# BMS_Rev3_SSR.net
KiCad netlist of a schematic drawn in EAGLE
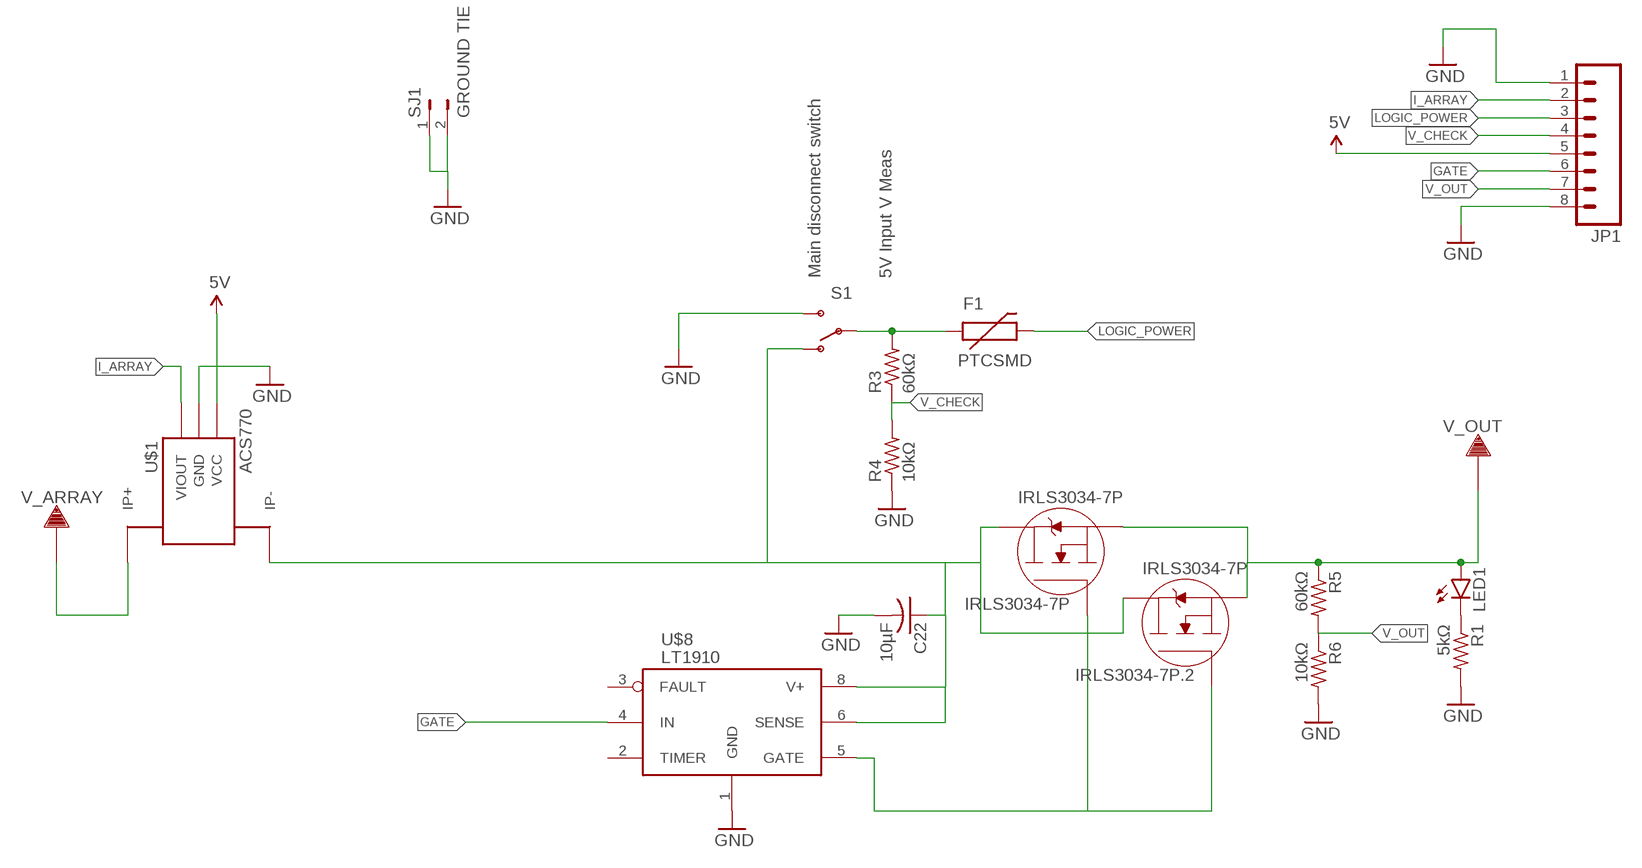
[diagram p0: schematic, sheet 1]

(export (version "E")
  (design (tool "Eeschema 10.0.6"))
  (components
    (comp (ref "C22")
      (value "10µF")
      (footprint "eagle-import:C1206")
      (libsource (lib "eagle-import") (part "C-USC1206"))
    )
    (comp (ref "F1")
      (value "PTCSMD")
      (footprint "eagle-import:PTC-1206")
      (libsource (lib "eagle-import") (part "PTCSMD"))
    )
    (comp (ref "IRLS3034-7P")
      (value "IRLS3034-7P")
      (footprint "eagle-import:D2PAK-7")
      (libsource (lib "eagle-import") (part "IRLS3034-7P"))
    )
    (comp (ref "IRLS3034-7P.2")
      (value "IRLS3034-7P")
      (footprint "eagle-import:D2PAK-7")
      (libsource (lib "eagle-import") (part "IRLS3034-7P"))
    )
    (comp (ref "JP1")
      (value "M08BM08B-SRSS-TB")
      (footprint "eagle-import:BM08B-SRSS-TB")
      (libsource (lib "eagle-import") (part "M08BM08B-SRSS-TB"))
    )
    (comp (ref "LED1")
      (value "LED1206")
      (footprint "eagle-import:LED-1206")
      (libsource (lib "eagle-import") (part "LED1206"))
    )
    (comp (ref "R1")
      (value "5kΩ")
      (footprint "eagle-import:R1206")
      (libsource (lib "eagle-import") (part "R-US_R1206"))
    )
    (comp (ref "R3")
      (value "60kΩ")
      (footprint "eagle-import:R1206")
      (libsource (lib "eagle-import") (part "R-US_R1206"))
    )
    (comp (ref "R4")
      (value "10kΩ")
      (footprint "eagle-import:R1206")
      (libsource (lib "eagle-import") (part "R-US_R1206"))
    )
    (comp (ref "R5")
      (value "60kΩ")
      (footprint "eagle-import:R1206")
      (libsource (lib "eagle-import") (part "R-US_R1206"))
    )
    (comp (ref "R6")
      (value "10kΩ")
      (footprint "eagle-import:R1206")
      (libsource (lib "eagle-import") (part "R-US_R1206"))
    )
    (comp (ref "S1")
      (value "SWITCH-SPDTPTH")
      (footprint "eagle-import:SWITCH-SPDT")
      (libsource (lib "eagle-import") (part "SWITCH-SPDTPTH"))
    )
    (comp (ref "SJ1")
      (value "GROUND TIE")
      (footprint "eagle-import:PTH-JUMPER-2-NO_NO_SILK")
      (libsource (lib "eagle-import") (part "JUMPER-PTH-2-NO"))
    )
    (comp (ref "U$1")
      (value "ACS770")
      (footprint "eagle-import:PFF_LEADFORM")
      (libsource (lib "eagle-import") (part "ACS770"))
    )
    (comp (ref "U$8")
      (value "LT1910")
      (footprint "eagle-import:SO8")
      (libsource (lib "eagle-import") (part "LT1910"))
    )
    (comp (ref "V_ARRAY")
      (value "TERMINAL_HOLE")
      (footprint "eagle-import:LARGE_TERMINAL_HOLE")
      (libsource (lib "eagle-import") (part "TERMINAL_HOLE"))
    )
    (comp (ref "V_OUT")
      (value "TERMINAL_HOLE")
      (footprint "eagle-import:LARGE_TERMINAL_HOLE")
      (libsource (lib "eagle-import") (part "TERMINAL_HOLE"))
    )
  )
  (nets
    (net (code "1") (name "5V") (class "Default")
      (node (ref "JP1") (pin "5") (pinfunction "5_5") (pintype "passive"))
      (node (ref "U$1") (pin "1") (pinfunction "VCC_1") (pintype "bidirectional"))
    )
    (net (code "2") (name "GATE") (class "Default")
      (node (ref "JP1") (pin "6") (pinfunction "6_6") (pintype "passive"))
      (node (ref "U$8") (pin "4") (pinfunction "IN_4") (pintype "bidirectional"))
    )
    (net (code "3") (name "GND") (class "Default")
      (node (ref "C22") (pin "2") (pinfunction "2_2") (pintype "passive"))
      (node (ref "JP1") (pin "1") (pinfunction "1_1") (pintype "passive"))
      (node (ref "JP1") (pin "8") (pinfunction "8_8") (pintype "passive"))
      (node (ref "R1") (pin "2") (pinfunction "2_2") (pintype "passive"))
      (node (ref "R4") (pin "1") (pinfunction "1_1") (pintype "passive"))
      (node (ref "R6") (pin "2") (pinfunction "2_2") (pintype "passive"))
      (node (ref "S1") (pin "3") (pinfunction "S_3") (pintype "passive"))
      (node (ref "SJ1") (pin "1") (pinfunction "1_1") (pintype "passive"))
      (node (ref "SJ1") (pin "2") (pinfunction "2_2") (pintype "passive"))
      (node (ref "U$1") (pin "2") (pinfunction "GND_2") (pintype "bidirectional"))
      (node (ref "U$8") (pin "1") (pinfunction "GND_1") (pintype "bidirectional"))
    )
    (net (code "4") (name "I_ARRAY") (class "Default")
      (node (ref "JP1") (pin "2") (pinfunction "2_2") (pintype "passive"))
      (node (ref "U$1") (pin "3") (pinfunction "VIOUT_3") (pintype "bidirectional"))
    )
    (net (code "5") (name "LOGIC_POWER") (class "Default")
      (node (ref "F1") (pin "2") (pinfunction "2_2") (pintype "bidirectional"))
      (node (ref "JP1") (pin "3") (pinfunction "3_3") (pintype "passive"))
    )
    (net (code "6") (name "Net-(IRLS3034-7P-DRAIN)") (class "Default")
      (node (ref "C22") (pin "1") (pinfunction "1_1") (pintype "passive"))
      (node (ref "IRLS3034-7P") (pin "PAD") (pinfunction "DRAIN_PAD") (pintype "bidirectional"))
      (node (ref "IRLS3034-7P.2") (pin "PAD") (pinfunction "DRAIN_PAD") (pintype "bidirectional"))
      (node (ref "S1") (pin "1") (pinfunction "O_1") (pintype "passive"))
      (node (ref "U$1") (pin "5_1") (pinfunction "IP-_5_1") (pintype "bidirectional"))
      (node (ref "U$1") (pin "5_10") (pinfunction "IP-_5_10") (pintype "bidirectional"))
      (node (ref "U$1") (pin "5_11") (pinfunction "IP-_5_11") (pintype "bidirectional"))
      (node (ref "U$1") (pin "5_12") (pinfunction "IP-_5_12") (pintype "bidirectional"))
      (node (ref "U$1") (pin "5_13") (pinfunction "IP-_5_13") (pintype "bidirectional"))
      (node (ref "U$1") (pin "5_14") (pinfunction "IP-_5_14") (pintype "bidirectional"))
      (node (ref "U$1") (pin "5_15") (pinfunction "IP-_5_15") (pintype "bidirectional"))
      (node (ref "U$1") (pin "5_16") (pinfunction "IP-_5_16") (pintype "bidirectional"))
      (node (ref "U$1") (pin "5_2") (pinfunction "IP-_5_2") (pintype "bidirectional"))
      (node (ref "U$1") (pin "5_3") (pinfunction "IP-_5_3") (pintype "bidirectional"))
      (node (ref "U$1") (pin "5_4") (pinfunction "IP-_5_4") (pintype "bidirectional"))
      (node (ref "U$1") (pin "5_5") (pinfunction "IP-_5_5") (pintype "bidirectional"))
      (node (ref "U$1") (pin "5_6") (pinfunction "IP-_5_6") (pintype "bidirectional"))
      (node (ref "U$1") (pin "5_7") (pinfunction "IP-_5_7") (pintype "bidirectional"))
      (node (ref "U$1") (pin "5_8") (pinfunction "IP-_5_8") (pintype "bidirectional"))
      (node (ref "U$1") (pin "5_9") (pinfunction "IP-_5_9") (pintype "bidirectional"))
      (node (ref "U$1") (pin "5_B") (pinfunction "IP-_5_B") (pintype "bidirectional"))
      (node (ref "U$1") (pin "5_T") (pinfunction "IP-_5_T") (pintype "bidirectional"))
      (node (ref "U$8") (pin "6") (pinfunction "SENSE_6") (pintype "bidirectional"))
      (node (ref "U$8") (pin "8") (pinfunction "V+_8") (pintype "bidirectional"))
    )
    (net (code "7") (name "Net-(IRLS3034-7P-GATE)") (class "Default")
      (node (ref "IRLS3034-7P") (pin "1") (pinfunction "GATE_1") (pintype "bidirectional"))
      (node (ref "IRLS3034-7P.2") (pin "1") (pinfunction "GATE_1") (pintype "bidirectional"))
      (node (ref "U$8") (pin "5") (pinfunction "GATE_5") (pintype "bidirectional"))
    )
    (net (code "8") (name "Net-(IRLS3034-7P-SOURCE-Pad2)") (class "Default")
      (node (ref "IRLS3034-7P") (pin "2") (pinfunction "SOURCE_2") (pintype "bidirectional"))
      (node (ref "IRLS3034-7P") (pin "3") (pinfunction "SOURCE_3") (pintype "bidirectional"))
      (node (ref "IRLS3034-7P") (pin "4") (pinfunction "SOURCE_4") (pintype "bidirectional"))
      (node (ref "IRLS3034-7P") (pin "5") (pinfunction "SOURCE_5") (pintype "bidirectional"))
      (node (ref "IRLS3034-7P") (pin "6") (pinfunction "SOURCE_6") (pintype "bidirectional"))
      (node (ref "IRLS3034-7P.2") (pin "2") (pinfunction "SOURCE_2") (pintype "bidirectional"))
      (node (ref "IRLS3034-7P.2") (pin "3") (pinfunction "SOURCE_3") (pintype "bidirectional"))
      (node (ref "IRLS3034-7P.2") (pin "4") (pinfunction "SOURCE_4") (pintype "bidirectional"))
      (node (ref "IRLS3034-7P.2") (pin "5") (pinfunction "SOURCE_5") (pintype "bidirectional"))
      (node (ref "IRLS3034-7P.2") (pin "6") (pinfunction "SOURCE_6") (pintype "bidirectional"))
      (node (ref "LED1") (pin "A") (pinfunction "A_A") (pintype "passive"))
      (node (ref "R5") (pin "1") (pinfunction "1_1") (pintype "passive"))
      (node (ref "V_OUT") (pin "P$1") (pinfunction "P$1_P$1") (pintype "bidirectional"))
    )
    (net (code "9") (name "Net-(LED1-PadC)") (class "Default")
      (node (ref "LED1") (pin "C") (pinfunction "C_C") (pintype "passive"))
      (node (ref "R1") (pin "1") (pinfunction "1_1") (pintype "passive"))
    )
    (net (code "10") (name "Net-(S1-P)") (class "Default")
      (node (ref "F1") (pin "1") (pinfunction "1_1") (pintype "bidirectional"))
      (node (ref "R3") (pin "2") (pinfunction "2_2") (pintype "passive"))
      (node (ref "S1") (pin "2") (pinfunction "P_2") (pintype "passive"))
    )
    (net (code "11") (name "Net-(U$1-IP+-Pad4_1)") (class "Default")
      (node (ref "U$1") (pin "4_1") (pinfunction "IP+_4_1") (pintype "bidirectional"))
      (node (ref "U$1") (pin "4_10") (pinfunction "IP+_4_10") (pintype "bidirectional"))
      (node (ref "U$1") (pin "4_11") (pinfunction "IP+_4_11") (pintype "bidirectional"))
      (node (ref "U$1") (pin "4_12") (pinfunction "IP+_4_12") (pintype "bidirectional"))
      (node (ref "U$1") (pin "4_13") (pinfunction "IP+_4_13") (pintype "bidirectional"))
      (node (ref "U$1") (pin "4_14") (pinfunction "IP+_4_14") (pintype "bidirectional"))
      (node (ref "U$1") (pin "4_15") (pinfunction "IP+_4_15") (pintype "bidirectional"))
      (node (ref "U$1") (pin "4_16") (pinfunction "IP+_4_16") (pintype "bidirectional"))
      (node (ref "U$1") (pin "4_2") (pinfunction "IP+_4_2") (pintype "bidirectional"))
      (node (ref "U$1") (pin "4_3") (pinfunction "IP+_4_3") (pintype "bidirectional"))
      (node (ref "U$1") (pin "4_4") (pinfunction "IP+_4_4") (pintype "bidirectional"))
      (node (ref "U$1") (pin "4_5") (pinfunction "IP+_4_5") (pintype "bidirectional"))
      (node (ref "U$1") (pin "4_6") (pinfunction "IP+_4_6") (pintype "bidirectional"))
      (node (ref "U$1") (pin "4_7") (pinfunction "IP+_4_7") (pintype "bidirectional"))
      (node (ref "U$1") (pin "4_8") (pinfunction "IP+_4_8") (pintype "bidirectional"))
      (node (ref "U$1") (pin "4_9") (pinfunction "IP+_4_9") (pintype "bidirectional"))
      (node (ref "U$1") (pin "4_B") (pinfunction "IP+_4_B") (pintype "bidirectional"))
      (node (ref "U$1") (pin "4_T") (pinfunction "IP+_4_T") (pintype "bidirectional"))
      (node (ref "V_ARRAY") (pin "P$1") (pinfunction "P$1_P$1") (pintype "bidirectional"))
    )
    (net (code "12") (name "V_CHECK") (class "Default")
      (node (ref "JP1") (pin "4") (pinfunction "4_4") (pintype "passive"))
      (node (ref "R3") (pin "1") (pinfunction "1_1") (pintype "passive"))
      (node (ref "R4") (pin "2") (pinfunction "2_2") (pintype "passive"))
    )
    (net (code "13") (name "V_OUT") (class "Default")
      (node (ref "JP1") (pin "7") (pinfunction "7_7") (pintype "passive"))
      (node (ref "R5") (pin "2") (pinfunction "2_2") (pintype "passive"))
      (node (ref "R6") (pin "1") (pinfunction "1_1") (pintype "passive"))
    )
    (net (code "14") (name "unconnected-(U$8-FAULT-Pad3)") (class "Default")
      (node (ref "U$8") (pin "3") (pinfunction "FAULT_3") (pintype "bidirectional"))
    )
    (net (code "15") (name "unconnected-(U$8-TIMER-Pad2)") (class "Default")
      (node (ref "U$8") (pin "2") (pinfunction "TIMER_2") (pintype "bidirectional"))
    )
  )
)
